# ACS_5_4.net
KiCad netlist of a schematic drawn in EAGLE
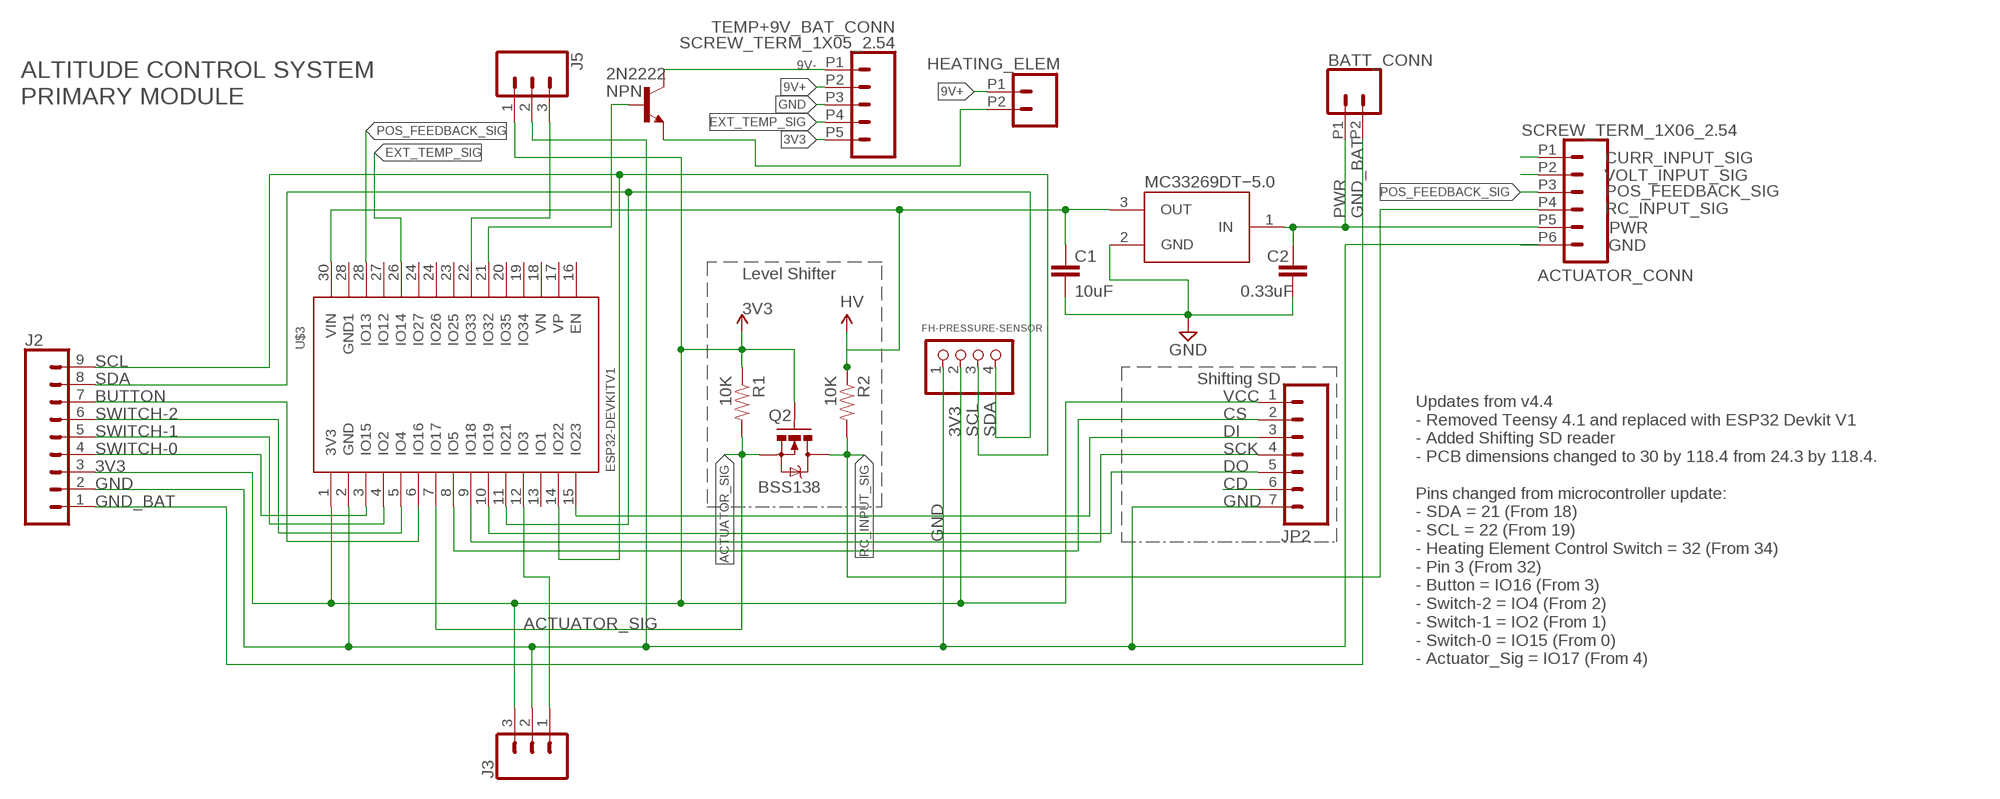
[diagram p0: schematic, sheet 1]

(export (version "E")
  (design (tool "Eeschema 10.0.6"))
  (components
    (comp (ref "2N2222")
      (value "NPN")
      (footprint "eagle-import:SOT95P237X112-3N")
      (libsource (lib "eagle-import") (part "NPNSOT23_"))
    )
    (comp (ref "ACTUATOR_CONN")
      (value "SCREW_TERM_1X06_2.54")
      (footprint "eagle-import:1X06_2.54_SCREWTERM")
      (libsource (lib "eagle-import") (part "SCREW_TERM_1X06_2.54"))
    )
    (comp (ref "BATT_CONN")
      (value "CONN_022.54MM_SCREWTERM")
      (footprint "eagle-import:1X02_2.54_SCREWTERM")
      (libsource (lib "eagle-import") (part "CONN_022.54MM_SCREWTERM"))
    )
    (comp (ref "C1")
      (value "10uF")
      (footprint "eagle-import:CAPC1608X85")
      (libsource (lib "eagle-import") (part "CCHIP-0603(1608-METRIC)_"))
    )
    (comp (ref "C2")
      (value "0.33uF")
      (footprint "eagle-import:CAPC1608X85")
      (libsource (lib "eagle-import") (part "CCHIP-0603(1608-METRIC)_"))
    )
    (comp (ref "FH-PRESSURE-SENSOR")
      (value "PINHD-1X4")
      (footprint "eagle-import:1X04")
      (libsource (lib "eagle-import") (part "PINHD-1X4"))
    )
    (comp (ref "HEATING_ELEM")
      (value "CONN_022.54MM_SCREWTERM")
      (footprint "eagle-import:1X02_2.54_SCREWTERM")
      (libsource (lib "eagle-import") (part "CONN_022.54MM_SCREWTERM"))
    )
    (comp (ref "J2")
      (value "CONN_09")
      (footprint "eagle-import:1X09")
      (libsource (lib "eagle-import") (part "CONN_09"))
    )
    (comp (ref "J3")
      (value "CONN_03")
      (footprint "eagle-import:1X03")
      (libsource (lib "eagle-import") (part "CONN_03"))
    )
    (comp (ref "J5")
      (value "CONN_03")
      (footprint "eagle-import:1X03")
      (libsource (lib "eagle-import") (part "CONN_03"))
    )
    (comp (ref "JP2")
      (value "M07")
      (footprint "eagle-import:1X07")
      (libsource (lib "eagle-import") (part "M07"))
    )
    (comp (ref "Q2")
      (value "BSS138")
      (footprint "eagle-import:SOT23-3")
      (libsource (lib "eagle-import") (part "MOSFET-NCHANNELSMD"))
    )
    (comp (ref "R1")
      (value "10K")
      (footprint "eagle-import:0603-RES")
      (libsource (lib "eagle-import") (part "RESISTOR0603-RES"))
    )
    (comp (ref "R2")
      (value "10K")
      (footprint "eagle-import:0603-RES")
      (libsource (lib "eagle-import") (part "RESISTOR0603-RES"))
    )
    (comp (ref "TEMP+9V_BAT_CONN")
      (value "SCREW_TERM_1X05_2.54")
      (footprint "eagle-import:1X05_2.54_SCREWTERM")
      (libsource (lib "eagle-import") (part "SCREW_TERM_1X05_2.54"))
    )
    (comp (ref "U$3")
      (value "ESP32DEVKITV1")
      (footprint "eagle-import:ESP32-DEVKITV1")
      (libsource (lib "eagle-import") (part "ESP32DEVKITV1"))
    )
    (comp (ref "U1")
      (value "MC78M05BDTRKG")
      (footprint "eagle-import:MC78M05BDTRKG")
      (fields
        (field (name "MANUFACTURER") "ON Semiconductor")
        (field (name "MPN") "IC REG LINEAR 5V 500MA DPAK")
        (field (name "CREATED_BY") "PCBLayout.com")
      )
      (libsource (lib "eagle-import") (part "MC78M05BDTRKG"))
    )
  )
  (nets
    (net (code "1") (name "/9V-") (class "Default")
      (node (ref "2N2222") (pin "3") (pinfunction "C_3") (pintype "passive"))
      (node (ref "TEMP+9V_BAT_CONN") (pin "P1") (pinfunction "1_P1") (pintype "passive"))
    )
    (net (code "2") (name "/BUTTON") (class "Default")
      (node (ref "J2") (pin "7") (pinfunction "7_7") (pintype "passive"))
      (node (ref "U$3") (pin "6") (pinfunction "IO16_6") (pintype "bidirectional"))
    )
    (net (code "3") (name "/CURR_INPUT_SIG") (class "Default")
      (node (ref "ACTUATOR_CONN") (pin "P1") (pinfunction "1_P1") (pintype "passive"))
    )
    (net (code "4") (name "/GND_BAT") (class "Default")
      (node (ref "BATT_CONN") (pin "P2") (pinfunction "2_P2") (pintype "passive"))
      (node (ref "J2") (pin "1") (pinfunction "1_1") (pintype "passive"))
    )
    (net (code "5") (name "/PWR") (class "Default")
      (node (ref "ACTUATOR_CONN") (pin "P5") (pinfunction "5_P5") (pintype "passive"))
      (node (ref "BATT_CONN") (pin "P1") (pinfunction "1_P1") (pintype "passive"))
      (node (ref "C2") (pin "1") (pinfunction "1_1") (pintype "passive"))
      (node (ref "U1") (pin "1") (pinfunction "IN_1") (pintype "input"))
    )
    (net (code "6") (name "/SCL") (class "Default")
      (node (ref "FH-PRESSURE-SENSOR") (pin "3") (pinfunction "3_3") (pintype "passive"))
      (node (ref "J2") (pin "9") (pinfunction "9_9") (pintype "passive"))
      (node (ref "U$3") (pin "14") (pinfunction "IO22_14") (pintype "bidirectional"))
    )
    (net (code "7") (name "/SDA") (class "Default")
      (node (ref "FH-PRESSURE-SENSOR") (pin "4") (pinfunction "4_4") (pintype "passive"))
      (node (ref "J2") (pin "8") (pinfunction "8_8") (pintype "passive"))
      (node (ref "U$3") (pin "11") (pinfunction "IO21_11") (pintype "bidirectional"))
    )
    (net (code "8") (name "/SWITCH-0") (class "Default")
      (node (ref "J2") (pin "4") (pinfunction "4_4") (pintype "passive"))
      (node (ref "U$3") (pin "3") (pinfunction "IO15_3") (pintype "bidirectional"))
    )
    (net (code "9") (name "/SWITCH-1") (class "Default")
      (node (ref "J2") (pin "5") (pinfunction "5_5") (pintype "passive"))
      (node (ref "U$3") (pin "4") (pinfunction "IO2_4") (pintype "bidirectional"))
    )
    (net (code "10") (name "/SWITCH-2") (class "Default")
      (node (ref "J2") (pin "6") (pinfunction "6_6") (pintype "passive"))
      (node (ref "U$3") (pin "5") (pinfunction "IO4_5") (pintype "bidirectional"))
    )
    (net (code "11") (name "/VOLT_INPUT_SIG") (class "Default")
      (node (ref "ACTUATOR_CONN") (pin "P2") (pinfunction "2_P2") (pintype "passive"))
    )
    (net (code "12") (name "3V3") (class "Default")
      (node (ref "FH-PRESSURE-SENSOR") (pin "2") (pinfunction "2_2") (pintype "passive"))
      (node (ref "J2") (pin "3") (pinfunction "3_3") (pintype "passive"))
      (node (ref "J3") (pin "3") (pinfunction "3_3") (pintype "passive"))
      (node (ref "J5") (pin "1") (pinfunction "1_1") (pintype "passive"))
      (node (ref "JP2") (pin "1") (pinfunction "1_1") (pintype "passive"))
      (node (ref "Q2") (pin "1") (pinfunction "G_1") (pintype "passive"))
      (node (ref "R1") (pin "1") (pinfunction "1_1") (pintype "passive"))
      (node (ref "TEMP+9V_BAT_CONN") (pin "P5") (pinfunction "5_P5") (pintype "passive"))
      (node (ref "U$3") (pin "1") (pinfunction "3V3_1") (pintype "bidirectional"))
    )
    (net (code "13") (name "9V+") (class "Default")
      (node (ref "HEATING_ELEM") (pin "P1") (pinfunction "1_P1") (pintype "passive"))
      (node (ref "TEMP+9V_BAT_CONN") (pin "P2") (pinfunction "2_P2") (pintype "passive"))
    )
    (net (code "14") (name "ACTUATOR_SIG") (class "Default")
      (node (ref "Q2") (pin "2") (pinfunction "S_2") (pintype "passive"))
      (node (ref "R1") (pin "2") (pinfunction "2_2") (pintype "passive"))
      (node (ref "U$3") (pin "7") (pinfunction "IO17_7") (pintype "bidirectional"))
    )
    (net (code "15") (name "EXT_TEMP_SIG") (class "Default")
      (node (ref "TEMP+9V_BAT_CONN") (pin "P4") (pinfunction "4_P4") (pintype "passive"))
      (node (ref "U$3") (pin "26") (pinfunction "IO14_26") (pintype "bidirectional"))
    )
    (net (code "16") (name "GND") (class "Default")
      (node (ref "ACTUATOR_CONN") (pin "P6") (pinfunction "6_P6") (pintype "passive"))
      (node (ref "C1") (pin "2") (pinfunction "2_2") (pintype "passive"))
      (node (ref "C2") (pin "2") (pinfunction "2_2") (pintype "passive"))
      (node (ref "FH-PRESSURE-SENSOR") (pin "1") (pinfunction "1_1") (pintype "passive"))
      (node (ref "J2") (pin "2") (pinfunction "2_2") (pintype "passive"))
      (node (ref "J3") (pin "2") (pinfunction "2_2") (pintype "passive"))
      (node (ref "J5") (pin "2") (pinfunction "2_2") (pintype "passive"))
      (node (ref "JP2") (pin "7") (pinfunction "7_7") (pintype "passive"))
      (node (ref "TEMP+9V_BAT_CONN") (pin "P3") (pinfunction "3_P3") (pintype "passive"))
      (node (ref "U$3") (pin "2") (pinfunction "GND_2") (pintype "bidirectional"))
      (node (ref "U1") (pin "2") (pinfunction "GND_2") (pintype "power_in"))
    )
    (net (code "17") (name "HV") (class "Default")
      (node (ref "C1") (pin "1") (pinfunction "1_1") (pintype "passive"))
      (node (ref "R2") (pin "1") (pinfunction "1_1") (pintype "passive"))
      (node (ref "U$3") (pin "30") (pinfunction "VIN_30") (pintype "bidirectional"))
      (node (ref "U1") (pin "3") (pinfunction "OUT_3") (pintype "output"))
    )
    (net (code "18") (name "Net-(2N2222-B)") (class "Default")
      (node (ref "2N2222") (pin "2") (pinfunction "B_2") (pintype "passive"))
      (node (ref "U$3") (pin "21") (pinfunction "IO32_21") (pintype "bidirectional"))
    )
    (net (code "19") (name "Net-(2N2222-E)") (class "Default")
      (node (ref "2N2222") (pin "1") (pinfunction "E_1") (pintype "passive"))
      (node (ref "HEATING_ELEM") (pin "P2") (pinfunction "2_P2") (pintype "passive"))
    )
    (net (code "20") (name "Net-(U$3-IO3)") (class "Default")
      (node (ref "J3") (pin "1") (pinfunction "1_1") (pintype "passive"))
      (node (ref "U$3") (pin "12") (pinfunction "IO3_12") (pintype "bidirectional"))
    )
    (net (code "21") (name "Net-(U$3-IO5)") (class "Default")
      (node (ref "JP2") (pin "2") (pinfunction "2_2") (pintype "passive"))
      (node (ref "U$3") (pin "8") (pinfunction "IO5_8") (pintype "bidirectional"))
    )
    (net (code "22") (name "Net-(U$3-IO18)") (class "Default")
      (node (ref "JP2") (pin "4") (pinfunction "4_4") (pintype "passive"))
      (node (ref "U$3") (pin "9") (pinfunction "IO18_9") (pintype "bidirectional"))
    )
    (net (code "23") (name "Net-(U$3-IO19)") (class "Default")
      (node (ref "JP2") (pin "5") (pinfunction "5_5") (pintype "passive"))
      (node (ref "U$3") (pin "10") (pinfunction "IO19_10") (pintype "bidirectional"))
    )
    (net (code "24") (name "Net-(U$3-IO23)") (class "Default")
      (node (ref "JP2") (pin "3") (pinfunction "3_3") (pintype "passive"))
      (node (ref "U$3") (pin "15") (pinfunction "IO23_15") (pintype "bidirectional"))
    )
    (net (code "25") (name "Net-(U$3-IO33)") (class "Default")
      (node (ref "J5") (pin "3") (pinfunction "3_3") (pintype "passive"))
      (node (ref "U$3") (pin "22") (pinfunction "IO33_22") (pintype "bidirectional"))
    )
    (net (code "26") (name "POS_FEEDBACK_SIG") (class "Default")
      (node (ref "ACTUATOR_CONN") (pin "P3") (pinfunction "3_P3") (pintype "passive"))
      (node (ref "U$3") (pin "28") (pinfunction "IO13_28") (pintype "bidirectional"))
    )
    (net (code "27") (name "RC_INPUT_SIG") (class "Default")
      (node (ref "ACTUATOR_CONN") (pin "P4") (pinfunction "4_P4") (pintype "passive"))
      (node (ref "Q2") (pin "3") (pinfunction "D_3") (pintype "passive"))
      (node (ref "R2") (pin "2") (pinfunction "2_2") (pintype "passive"))
    )
    (net (code "28") (name "unconnected-(JP2-Pad6)") (class "Default")
      (node (ref "JP2") (pin "6") (pinfunction "6_6") (pintype "passive"))
    )
    (net (code "29") (name "unconnected-(U$3-EN-Pad16)") (class "Default")
      (node (ref "U$3") (pin "16") (pinfunction "EN_16") (pintype "bidirectional"))
    )
    (net (code "30") (name "unconnected-(U$3-GND1-Pad28)") (class "Default")
      (node (ref "U$3") (pin "28") (pinfunction "GND1_28") (pintype "bidirectional"))
    )
    (net (code "31") (name "unconnected-(U$3-IO1-Pad13)") (class "Default")
      (node (ref "U$3") (pin "13") (pinfunction "IO1_13") (pintype "bidirectional"))
    )
    (net (code "32") (name "unconnected-(U$3-IO12-Pad27)") (class "Default")
      (node (ref "U$3") (pin "27") (pinfunction "IO12_27") (pintype "bidirectional"))
    )
    (net (code "33") (name "unconnected-(U$3-IO25-Pad23)") (class "Default")
      (node (ref "U$3") (pin "23") (pinfunction "IO25_23") (pintype "bidirectional"))
    )
    (net (code "34") (name "unconnected-(U$3-IO26-Pad24)") (class "Default")
      (node (ref "U$3") (pin "24") (pinfunction "IO26_24") (pintype "bidirectional"))
    )
    (net (code "35") (name "unconnected-(U$3-IO27-Pad24)") (class "Default")
      (node (ref "U$3") (pin "24") (pinfunction "IO27_24") (pintype "bidirectional"))
    )
    (net (code "36") (name "unconnected-(U$3-IO34-Pad19)") (class "Default")
      (node (ref "U$3") (pin "19") (pinfunction "IO34_19") (pintype "bidirectional"))
    )
    (net (code "37") (name "unconnected-(U$3-IO35-Pad20)") (class "Default")
      (node (ref "U$3") (pin "20") (pinfunction "IO35_20") (pintype "bidirectional"))
    )
    (net (code "38") (name "unconnected-(U$3-VN-Pad18)") (class "Default")
      (node (ref "U$3") (pin "18") (pinfunction "VN_18") (pintype "bidirectional"))
    )
    (net (code "39") (name "unconnected-(U$3-VP-Pad17)") (class "Default")
      (node (ref "U$3") (pin "17") (pinfunction "VP_17") (pintype "bidirectional"))
    )
  )
)
